# HBridges.net
KiCad netlist of a schematic drawn in Altium Designer
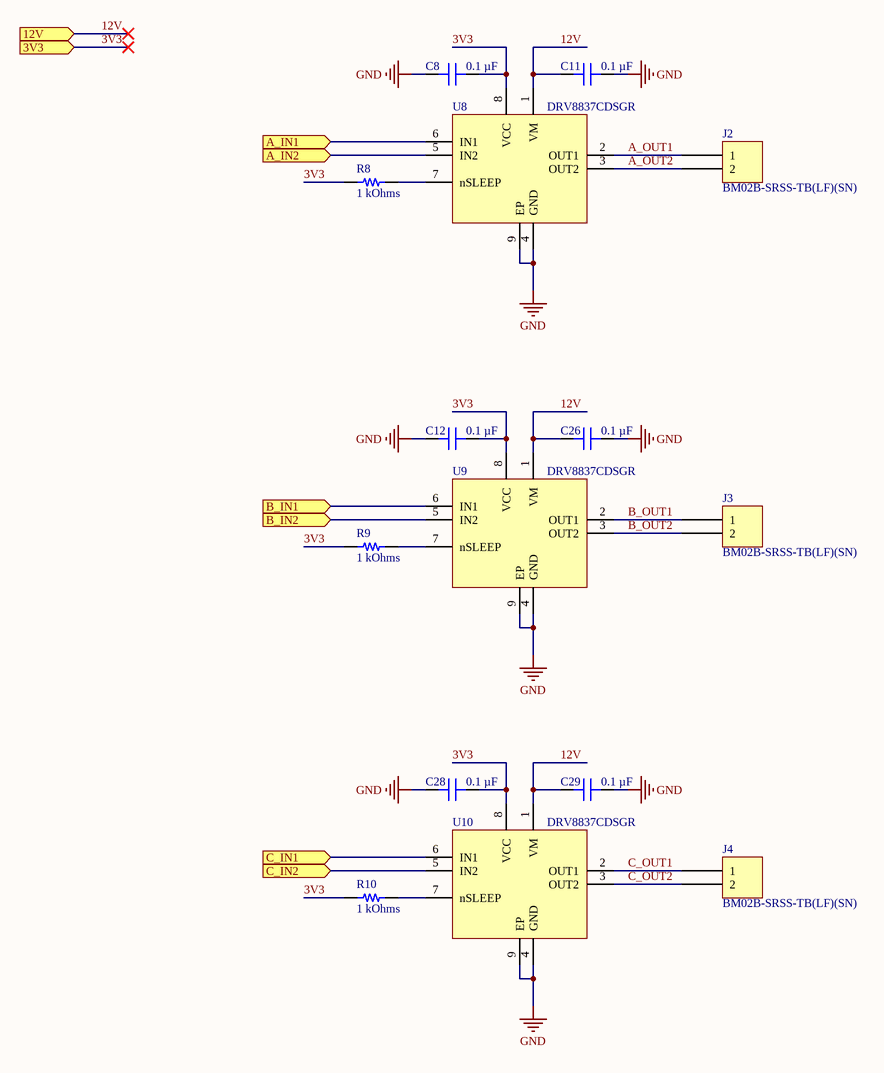
[diagram p0: HBridges.SchDoc]

(export (version "E")
  (design (tool "Eeschema 10.0.6"))
  (components
    (comp (ref "C8")
      (value "0.1 µF")
      (footprint "CAP 0402_1005")
      (description "CAP CER 0.1UF 16V X7R 0402")
      (fields (field (name "PART NUMBER") "C0402C104K4RACAUTO") (field (name "MANUFACTURER") "KEMET"))
      (libsource (lib "Celestial Altium Library - altium_library") (part "Capacitor"))
    )
    (comp (ref "C11")
      (value "0.1 µF")
      (footprint "CAP 0402_1005")
      (description "CAP CER 0.1UF 16V X7R 0402")
      (fields (field (name "PART NUMBER") "C0402C104K4RACAUTO") (field (name "MANUFACTURER") "KEMET"))
      (libsource (lib "Celestial Altium Library - altium_library") (part "Capacitor"))
    )
    (comp (ref "C12")
      (value "0.1 µF")
      (footprint "CAP 0402_1005")
      (description "CAP CER 0.1UF 16V X7R 0402")
      (fields (field (name "PART NUMBER") "C0402C104K4RACAUTO") (field (name "MANUFACTURER") "KEMET"))
      (libsource (lib "Celestial Altium Library - altium_library") (part "Capacitor"))
    )
    (comp (ref "C26")
      (value "0.1 µF")
      (footprint "CAP 0402_1005")
      (description "CAP CER 0.1UF 16V X7R 0402")
      (fields (field (name "PART NUMBER") "C0402C104K4RACAUTO") (field (name "MANUFACTURER") "KEMET"))
      (libsource (lib "Celestial Altium Library - altium_library") (part "Capacitor"))
    )
    (comp (ref "C28")
      (value "0.1 µF")
      (footprint "CAP 0402_1005")
      (description "CAP CER 0.1UF 16V X7R 0402")
      (fields (field (name "PART NUMBER") "C0402C104K4RACAUTO") (field (name "MANUFACTURER") "KEMET"))
      (libsource (lib "Celestial Altium Library - altium_library") (part "Capacitor"))
    )
    (comp (ref "C29")
      (value "0.1 µF")
      (footprint "CAP 0402_1005")
      (description "CAP CER 0.1UF 16V X7R 0402")
      (fields (field (name "PART NUMBER") "C0402C104K4RACAUTO") (field (name "MANUFACTURER") "KEMET"))
      (libsource (lib "Celestial Altium Library - altium_library") (part "Capacitor"))
    )
    (comp (ref "J2")
      (value "BM02B-SRSS-TB(LF)(SN)")
      (footprint "JST BM02B-SRSS-TB")
      (description "CONN HEADER SMD 2POS 1MM")
      (fields (field (name "MANUFACTURER") "JST Sales America Inc."))
      (libsource (lib "Celestial Altium Library - altium_library") (part "2 Pin"))
    )
    (comp (ref "J3")
      (value "BM02B-SRSS-TB(LF)(SN)")
      (footprint "JST BM02B-SRSS-TB")
      (description "CONN HEADER SMD 2POS 1MM")
      (fields (field (name "MANUFACTURER") "JST Sales America Inc."))
      (libsource (lib "Celestial Altium Library - altium_library") (part "2 Pin"))
    )
    (comp (ref "J4")
      (value "BM02B-SRSS-TB(LF)(SN)")
      (footprint "JST BM02B-SRSS-TB")
      (description "CONN HEADER SMD 2POS 1MM")
      (fields (field (name "MANUFACTURER") "JST Sales America Inc."))
      (libsource (lib "Celestial Altium Library - altium_library") (part "2 Pin"))
    )
    (comp (ref "R8")
      (value "1 kOhms")
      (footprint "YAGEO RES 0402_1005")
      (description "RES 1K OHM 1% 1/16W 0402")
      (fields (field (name "PART NUMBER") "RC0402FR-071KL") (field (name "MANUFACTURER") "Yageo"))
      (libsource (lib "Celestial Altium Library - altium_library") (part "Resistor"))
    )
    (comp (ref "R9")
      (value "1 kOhms")
      (footprint "YAGEO RES 0402_1005")
      (description "RES 1K OHM 1% 1/16W 0402")
      (fields (field (name "PART NUMBER") "RC0402FR-071KL") (field (name "MANUFACTURER") "Yageo"))
      (libsource (lib "Celestial Altium Library - altium_library") (part "Resistor"))
    )
    (comp (ref "R10")
      (value "1 kOhms")
      (footprint "YAGEO RES 0402_1005")
      (description "RES 1K OHM 1% 1/16W 0402")
      (fields (field (name "PART NUMBER") "RC0402FR-071KL") (field (name "MANUFACTURER") "Yageo"))
      (libsource (lib "Celestial Altium Library - altium_library") (part "Resistor"))
    )
    (comp (ref "U8")
      (value "DRV8837CDSGR")
      (footprint "SON50P200X200X80-9N")
      (description "11-V, 1-A H-bridge motor driver 8-WSON -40 to 85")
      (fields (field (name "MF") "Texas Instruments"))
      (libsource (lib "IC") (part "DRV8837CDSGR"))
    )
    (comp (ref "U9")
      (value "DRV8837CDSGR")
      (footprint "SON50P200X200X80-9N")
      (description "11-V, 1-A H-bridge motor driver 8-WSON -40 to 85")
      (fields (field (name "MF") "Texas Instruments"))
      (libsource (lib "IC") (part "DRV8837CDSGR"))
    )
    (comp (ref "U10")
      (value "DRV8837CDSGR")
      (footprint "SON50P200X200X80-9N")
      (description "11-V, 1-A H-bridge motor driver 8-WSON -40 to 85")
      (fields (field (name "MF") "Texas Instruments"))
      (libsource (lib "IC") (part "DRV8837CDSGR"))
    )
  )
  (nets
    (net (code "1") (name "/3V3") (class "Default")
      (node (ref "C12") (pin "1") (pinfunction "1_1") (pintype "passive"))
      (node (ref "C28") (pin "1") (pinfunction "1_1") (pintype "passive"))
      (node (ref "C8") (pin "1") (pinfunction "1_1") (pintype "passive"))
      (node (ref "R10") (pin "1") (pinfunction "1_1") (pintype "passive"))
      (node (ref "R8") (pin "1") (pinfunction "1_1") (pintype "passive"))
      (node (ref "R9") (pin "1") (pinfunction "1_1") (pintype "passive"))
      (node (ref "U10") (pin "8") (pinfunction "VCC_8") (pintype "power_in"))
      (node (ref "U8") (pin "8") (pinfunction "VCC_8") (pintype "power_in"))
      (node (ref "U9") (pin "8") (pinfunction "VCC_8") (pintype "power_in"))
    )
    (net (code "2") (name "/12V") (class "Default")
      (node (ref "C11") (pin "2") (pinfunction "2_2") (pintype "passive"))
      (node (ref "C26") (pin "2") (pinfunction "2_2") (pintype "passive"))
      (node (ref "C29") (pin "2") (pinfunction "2_2") (pintype "passive"))
      (node (ref "U10") (pin "1") (pinfunction "VM_1") (pintype "power_in"))
      (node (ref "U8") (pin "1") (pinfunction "VM_1") (pintype "power_in"))
      (node (ref "U9") (pin "1") (pinfunction "VM_1") (pintype "power_in"))
    )
    (net (code "3") (name "/A_IN1") (class "Default")
      (node (ref "U8") (pin "6") (pinfunction "IN1_6") (pintype "passive"))
    )
    (net (code "4") (name "/A_IN2") (class "Default")
      (node (ref "U8") (pin "5") (pinfunction "IN2_5") (pintype "passive"))
    )
    (net (code "5") (name "/A_OUT1") (class "Default")
      (node (ref "J2") (pin "1") (pinfunction "1_1") (pintype "passive"))
      (node (ref "U8") (pin "2") (pinfunction "OUT1_2") (pintype "passive"))
    )
    (net (code "6") (name "/A_OUT2") (class "Default")
      (node (ref "J2") (pin "2") (pinfunction "2_2") (pintype "passive"))
      (node (ref "U8") (pin "3") (pinfunction "OUT2_3") (pintype "passive"))
    )
    (net (code "7") (name "/B_IN1") (class "Default")
      (node (ref "U9") (pin "6") (pinfunction "IN1_6") (pintype "passive"))
    )
    (net (code "8") (name "/B_IN2") (class "Default")
      (node (ref "U9") (pin "5") (pinfunction "IN2_5") (pintype "passive"))
    )
    (net (code "9") (name "/B_OUT1") (class "Default")
      (node (ref "J3") (pin "1") (pinfunction "1_1") (pintype "passive"))
      (node (ref "U9") (pin "2") (pinfunction "OUT1_2") (pintype "passive"))
    )
    (net (code "10") (name "/B_OUT2") (class "Default")
      (node (ref "J3") (pin "2") (pinfunction "2_2") (pintype "passive"))
      (node (ref "U9") (pin "3") (pinfunction "OUT2_3") (pintype "passive"))
    )
    (net (code "11") (name "/C_IN1") (class "Default")
      (node (ref "U10") (pin "6") (pinfunction "IN1_6") (pintype "passive"))
    )
    (net (code "12") (name "/C_IN2") (class "Default")
      (node (ref "U10") (pin "5") (pinfunction "IN2_5") (pintype "passive"))
    )
    (net (code "13") (name "/C_OUT1") (class "Default")
      (node (ref "J4") (pin "1") (pinfunction "1_1") (pintype "passive"))
      (node (ref "U10") (pin "2") (pinfunction "OUT1_2") (pintype "passive"))
    )
    (net (code "14") (name "/C_OUT2") (class "Default")
      (node (ref "J4") (pin "2") (pinfunction "2_2") (pintype "passive"))
      (node (ref "U10") (pin "3") (pinfunction "OUT2_3") (pintype "passive"))
    )
    (net (code "15") (name "GND") (class "Default")
      (node (ref "C11") (pin "1") (pinfunction "1_1") (pintype "passive"))
      (node (ref "C12") (pin "2") (pinfunction "2_2") (pintype "passive"))
      (node (ref "C26") (pin "1") (pinfunction "1_1") (pintype "passive"))
      (node (ref "C28") (pin "2") (pinfunction "2_2") (pintype "passive"))
      (node (ref "C29") (pin "1") (pinfunction "1_1") (pintype "passive"))
      (node (ref "C8") (pin "2") (pinfunction "2_2") (pintype "passive"))
      (node (ref "U10") (pin "4") (pinfunction "GND_4") (pintype "power_in"))
      (node (ref "U10") (pin "9") (pinfunction "EP_9") (pintype "power_in"))
      (node (ref "U8") (pin "4") (pinfunction "GND_4") (pintype "power_in"))
      (node (ref "U8") (pin "9") (pinfunction "EP_9") (pintype "power_in"))
      (node (ref "U9") (pin "4") (pinfunction "GND_4") (pintype "power_in"))
      (node (ref "U9") (pin "9") (pinfunction "EP_9") (pintype "power_in"))
    )
    (net (code "16") (name "Net-(U8-nSLEEP)") (class "Default")
      (node (ref "R8") (pin "2") (pinfunction "2_2") (pintype "passive"))
      (node (ref "U8") (pin "7") (pinfunction "nSLEEP_7") (pintype "passive"))
    )
    (net (code "17") (name "Net-(U9-nSLEEP)") (class "Default")
      (node (ref "R9") (pin "2") (pinfunction "2_2") (pintype "passive"))
      (node (ref "U9") (pin "7") (pinfunction "nSLEEP_7") (pintype "passive"))
    )
    (net (code "18") (name "Net-(U10-nSLEEP)") (class "Default")
      (node (ref "R10") (pin "2") (pinfunction "2_2") (pintype "passive"))
      (node (ref "U10") (pin "7") (pinfunction "nSLEEP_7") (pintype "passive"))
    )
  )
)
